# connector.net
KiCad netlist of a schematic drawn in Altium Designer
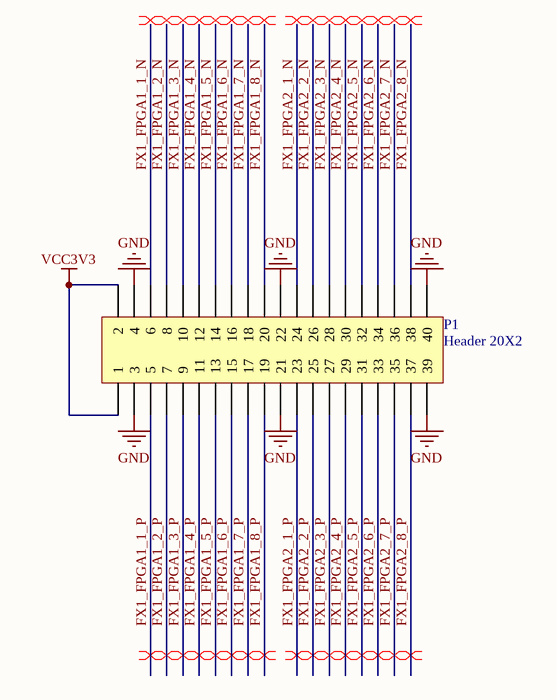
[diagram p0: connector.SchDoc]

(export (version "E")
  (design (tool "Eeschema 10.0.6"))
  (components
    (comp (ref "P1")
      (value "Header 20X2")
      (footprint "HDR2X20")
      (description "Header, 20-Pin, Dual row")
      (fields (field (name "PUBLISHER") "Altium Limited"))
      (libsource (lib "Miscellaneous Connectors") (part "Header 20X2"))
    )
  )
  (nets
    (net (code "1") (name "/FX1_FPGA1_1_N") (class "Default")
      (node (ref "P1") (pin "6") (pinfunction "6_6") (pintype "passive"))
    )
    (net (code "2") (name "/FX1_FPGA1_1_P") (class "Default")
      (node (ref "P1") (pin "5") (pinfunction "5_5") (pintype "passive"))
    )
    (net (code "3") (name "/FX1_FPGA1_2_N") (class "Default")
      (node (ref "P1") (pin "8") (pinfunction "8_8") (pintype "passive"))
    )
    (net (code "4") (name "/FX1_FPGA1_2_P") (class "Default")
      (node (ref "P1") (pin "7") (pinfunction "7_7") (pintype "passive"))
    )
    (net (code "5") (name "/FX1_FPGA1_3_N") (class "Default")
      (node (ref "P1") (pin "10") (pinfunction "10_10") (pintype "passive"))
    )
    (net (code "6") (name "/FX1_FPGA1_3_P") (class "Default")
      (node (ref "P1") (pin "9") (pinfunction "9_9") (pintype "passive"))
    )
    (net (code "7") (name "/FX1_FPGA1_4_N") (class "Default")
      (node (ref "P1") (pin "12") (pinfunction "12_12") (pintype "passive"))
    )
    (net (code "8") (name "/FX1_FPGA1_4_P") (class "Default")
      (node (ref "P1") (pin "11") (pinfunction "11_11") (pintype "passive"))
    )
    (net (code "9") (name "/FX1_FPGA1_5_N") (class "Default")
      (node (ref "P1") (pin "14") (pinfunction "14_14") (pintype "passive"))
    )
    (net (code "10") (name "/FX1_FPGA1_5_P") (class "Default")
      (node (ref "P1") (pin "13") (pinfunction "13_13") (pintype "passive"))
    )
    (net (code "11") (name "/FX1_FPGA1_6_N") (class "Default")
      (node (ref "P1") (pin "16") (pinfunction "16_16") (pintype "passive"))
    )
    (net (code "12") (name "/FX1_FPGA1_6_P") (class "Default")
      (node (ref "P1") (pin "15") (pinfunction "15_15") (pintype "passive"))
    )
    (net (code "13") (name "/FX1_FPGA1_7_N") (class "Default")
      (node (ref "P1") (pin "18") (pinfunction "18_18") (pintype "passive"))
    )
    (net (code "14") (name "/FX1_FPGA1_7_P") (class "Default")
      (node (ref "P1") (pin "17") (pinfunction "17_17") (pintype "passive"))
    )
    (net (code "15") (name "/FX1_FPGA1_8_N") (class "Default")
      (node (ref "P1") (pin "20") (pinfunction "20_20") (pintype "passive"))
    )
    (net (code "16") (name "/FX1_FPGA1_8_P") (class "Default")
      (node (ref "P1") (pin "19") (pinfunction "19_19") (pintype "passive"))
    )
    (net (code "17") (name "/FX1_FPGA2_1_N") (class "Default")
      (node (ref "P1") (pin "24") (pinfunction "24_24") (pintype "passive"))
    )
    (net (code "18") (name "/FX1_FPGA2_1_P") (class "Default")
      (node (ref "P1") (pin "23") (pinfunction "23_23") (pintype "passive"))
    )
    (net (code "19") (name "/FX1_FPGA2_2_N") (class "Default")
      (node (ref "P1") (pin "26") (pinfunction "26_26") (pintype "passive"))
    )
    (net (code "20") (name "/FX1_FPGA2_2_P") (class "Default")
      (node (ref "P1") (pin "25") (pinfunction "25_25") (pintype "passive"))
    )
    (net (code "21") (name "/FX1_FPGA2_3_N") (class "Default")
      (node (ref "P1") (pin "28") (pinfunction "28_28") (pintype "passive"))
    )
    (net (code "22") (name "/FX1_FPGA2_3_P") (class "Default")
      (node (ref "P1") (pin "27") (pinfunction "27_27") (pintype "passive"))
    )
    (net (code "23") (name "/FX1_FPGA2_4_N") (class "Default")
      (node (ref "P1") (pin "30") (pinfunction "30_30") (pintype "passive"))
    )
    (net (code "24") (name "/FX1_FPGA2_4_P") (class "Default")
      (node (ref "P1") (pin "29") (pinfunction "29_29") (pintype "passive"))
    )
    (net (code "25") (name "/FX1_FPGA2_5_N") (class "Default")
      (node (ref "P1") (pin "32") (pinfunction "32_32") (pintype "passive"))
    )
    (net (code "26") (name "/FX1_FPGA2_5_P") (class "Default")
      (node (ref "P1") (pin "31") (pinfunction "31_31") (pintype "passive"))
    )
    (net (code "27") (name "/FX1_FPGA2_6_N") (class "Default")
      (node (ref "P1") (pin "34") (pinfunction "34_34") (pintype "passive"))
    )
    (net (code "28") (name "/FX1_FPGA2_6_P") (class "Default")
      (node (ref "P1") (pin "33") (pinfunction "33_33") (pintype "passive"))
    )
    (net (code "29") (name "/FX1_FPGA2_7_N") (class "Default")
      (node (ref "P1") (pin "36") (pinfunction "36_36") (pintype "passive"))
    )
    (net (code "30") (name "/FX1_FPGA2_7_P") (class "Default")
      (node (ref "P1") (pin "35") (pinfunction "35_35") (pintype "passive"))
    )
    (net (code "31") (name "/FX1_FPGA2_8_N") (class "Default")
      (node (ref "P1") (pin "38") (pinfunction "38_38") (pintype "passive"))
    )
    (net (code "32") (name "/FX1_FPGA2_8_P") (class "Default")
      (node (ref "P1") (pin "37") (pinfunction "37_37") (pintype "passive"))
    )
    (net (code "33") (name "GND") (class "Default")
      (node (ref "P1") (pin "21") (pinfunction "21_21") (pintype "passive"))
      (node (ref "P1") (pin "22") (pinfunction "22_22") (pintype "passive"))
      (node (ref "P1") (pin "3") (pinfunction "3_3") (pintype "passive"))
      (node (ref "P1") (pin "39") (pinfunction "39_39") (pintype "passive"))
      (node (ref "P1") (pin "4") (pinfunction "4_4") (pintype "passive"))
      (node (ref "P1") (pin "40") (pinfunction "40_40") (pintype "passive"))
    )
    (net (code "34") (name "VCC3V3") (class "Default")
      (node (ref "P1") (pin "1") (pinfunction "1_1") (pintype "passive"))
      (node (ref "P1") (pin "2") (pinfunction "2_2") (pintype "passive"))
    )
  )
)
